# POWER.net
KiCad netlist of a schematic drawn in Altium Designer
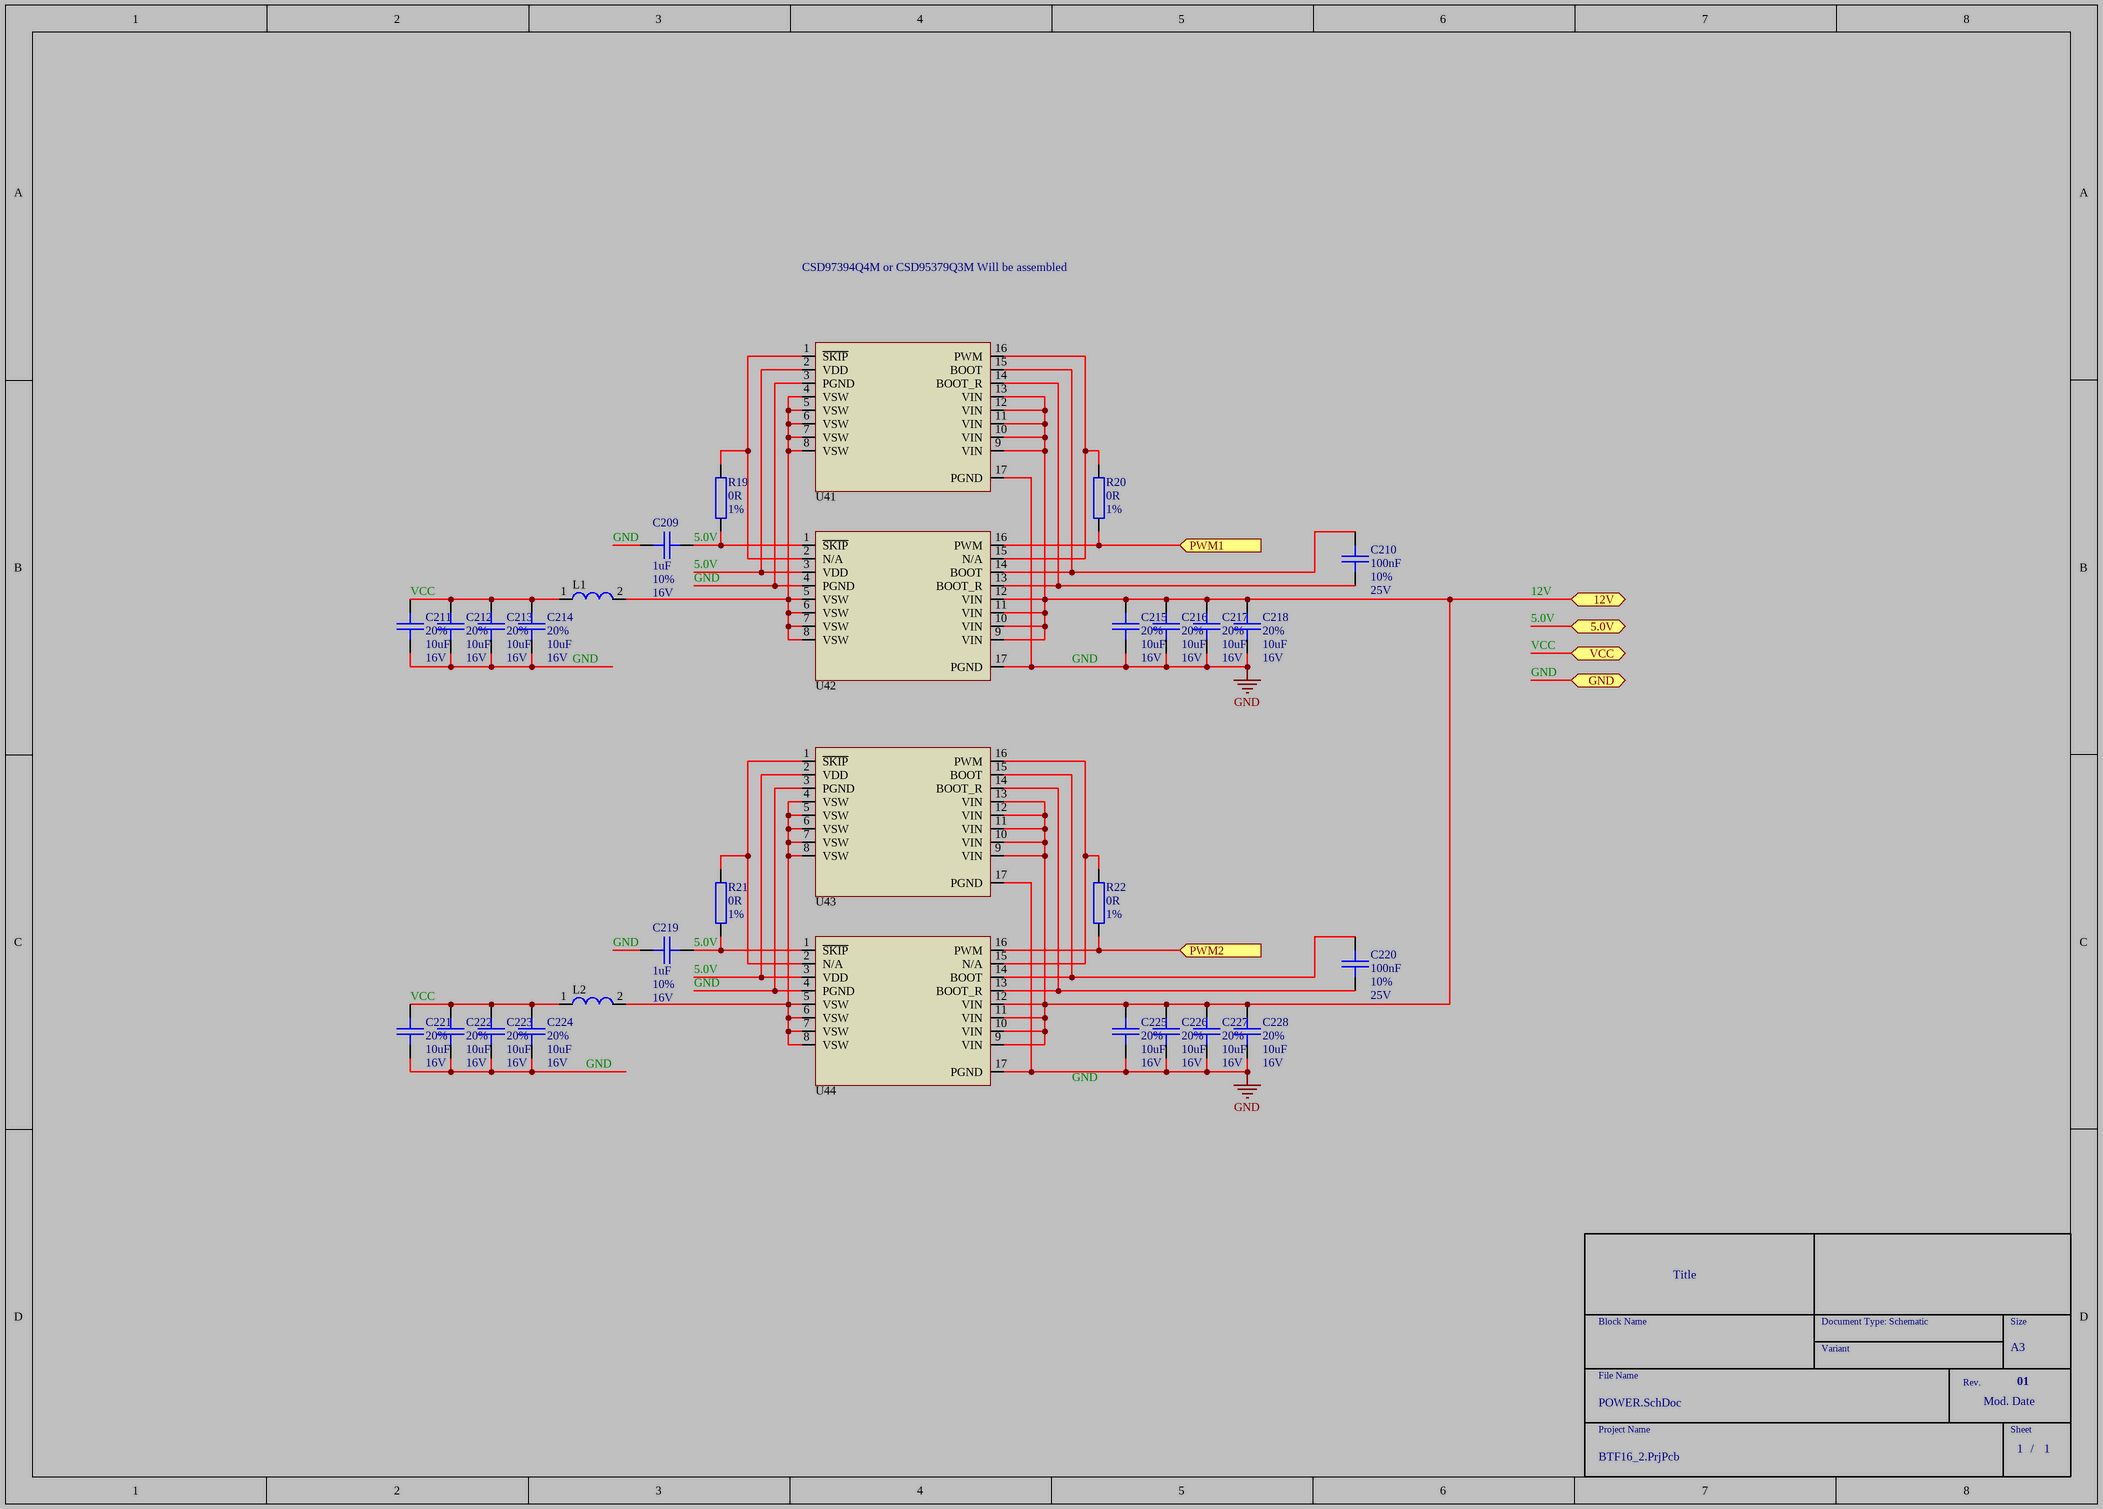
[diagram p0: POWER.SchDoc]

(export (version "E")
  (design (tool "Eeschema 10.0.6"))
  (components
    (comp (ref "C209")
      (value "C")
      (footprint "SMD_0603_CAPC1608X95N")
      (fields
        (field (name "DB_PART_NUMBER") "CAP000023307")
        (field (name "DB_VALUE") "1uF")
        (field (name "DB_TOLERANCE") "10%")
        (field (name "DB_VOLTAGE") "16V")
        (field (name "DB_MANUFACTURER_PART") "KEMET    C0603F105K4RAC")
      )
      (libsource (lib "Database_Libs1") (part "C"))
    )
    (comp (ref "C210")
      (value "C")
      (footprint "SMD_0402_CAPC1005X55N")
      (fields
        (field (name "DB_PART_NUMBER") "CAP000047469")
        (field (name "DB_VALUE") "100nF")
        (field (name "DB_TOLERANCE") "10%")
        (field (name "DB_VOLTAGE") "25V")
        (field (name "DB_MANUFACTURER_PART") "SAMSUNG    CL05A104KA5NNNC")
        (field (name "DB_APPROVED_BY") "VSN")
      )
      (libsource (lib "Database_Libs1") (part "C"))
    )
    (comp (ref "C211")
      (value "C")
      (footprint "SMD_0805_CAPC2012X145N")
      (fields
        (field (name "DB_MANUFACTURER_PART") "KEMET    C0805C106M4PAC")
        (field (name "DB_PART_NUMBER") "CAP000043650")
        (field (name "DB_TOLERANCE") "20%")
        (field (name "DB_VALUE") "10uF")
        (field (name "DB_VOLTAGE") "16V")
      )
      (libsource (lib "Database_Libs1") (part "C"))
    )
    (comp (ref "C212")
      (value "C")
      (footprint "SMD_0805_CAPC2012X145N")
      (fields
        (field (name "DB_MANUFACTURER_PART") "KEMET    C0805C106M4PAC")
        (field (name "DB_PART_NUMBER") "CAP000043650")
        (field (name "DB_TOLERANCE") "20%")
        (field (name "DB_VALUE") "10uF")
        (field (name "DB_VOLTAGE") "16V")
      )
      (libsource (lib "Database_Libs1") (part "C"))
    )
    (comp (ref "C213")
      (value "C")
      (footprint "SMD_0805_CAPC2012X145N")
      (fields
        (field (name "DB_MANUFACTURER_PART") "KEMET    C0805C106M4PAC")
        (field (name "DB_PART_NUMBER") "CAP000043650")
        (field (name "DB_TOLERANCE") "20%")
        (field (name "DB_VALUE") "10uF")
        (field (name "DB_VOLTAGE") "16V")
      )
      (libsource (lib "Database_Libs1") (part "C"))
    )
    (comp (ref "C214")
      (value "C")
      (footprint "SMD_0805_CAPC2012X145N")
      (fields
        (field (name "DB_MANUFACTURER_PART") "KEMET    C0805C106M4PAC")
        (field (name "DB_PART_NUMBER") "CAP000043650")
        (field (name "DB_TOLERANCE") "20%")
        (field (name "DB_VALUE") "10uF")
        (field (name "DB_VOLTAGE") "16V")
      )
      (libsource (lib "Database_Libs1") (part "C"))
    )
    (comp (ref "C215")
      (value "C")
      (footprint "SMD_0805_CAPC2012X145N")
      (fields
        (field (name "DB_MANUFACTURER_PART") "KEMET    C0805C106M4PAC")
        (field (name "DB_PART_NUMBER") "CAP000043650")
        (field (name "DB_TOLERANCE") "20%")
        (field (name "DB_VALUE") "10uF")
        (field (name "DB_VOLTAGE") "16V")
      )
      (libsource (lib "Database_Libs1") (part "C"))
    )
    (comp (ref "C216")
      (value "C")
      (footprint "SMD_0805_CAPC2012X145N")
      (fields
        (field (name "DB_MANUFACTURER_PART") "KEMET    C0805C106M4PAC")
        (field (name "DB_PART_NUMBER") "CAP000043650")
        (field (name "DB_TOLERANCE") "20%")
        (field (name "DB_VALUE") "10uF")
        (field (name "DB_VOLTAGE") "16V")
      )
      (libsource (lib "Database_Libs1") (part "C"))
    )
    (comp (ref "C217")
      (value "C")
      (footprint "SMD_0805_CAPC2012X145N")
      (fields
        (field (name "DB_MANUFACTURER_PART") "KEMET    C0805C106M4PAC")
        (field (name "DB_PART_NUMBER") "CAP000043650")
        (field (name "DB_TOLERANCE") "20%")
        (field (name "DB_VALUE") "10uF")
        (field (name "DB_VOLTAGE") "16V")
      )
      (libsource (lib "Database_Libs1") (part "C"))
    )
    (comp (ref "C218")
      (value "C")
      (footprint "SMD_0805_CAPC2012X145N")
      (fields
        (field (name "DB_MANUFACTURER_PART") "KEMET    C0805C106M4PAC")
        (field (name "DB_PART_NUMBER") "CAP000043650")
        (field (name "DB_TOLERANCE") "20%")
        (field (name "DB_VALUE") "10uF")
        (field (name "DB_VOLTAGE") "16V")
      )
      (libsource (lib "Database_Libs1") (part "C"))
    )
    (comp (ref "C219")
      (value "C")
      (footprint "SMD_0603_CAPC1608X95N")
      (fields
        (field (name "DB_PART_NUMBER") "CAP000023307")
        (field (name "DB_VALUE") "1uF")
        (field (name "DB_TOLERANCE") "10%")
        (field (name "DB_VOLTAGE") "16V")
        (field (name "DB_MANUFACTURER_PART") "KEMET    C0603F105K4RAC")
      )
      (libsource (lib "Database_Libs1") (part "C"))
    )
    (comp (ref "C220")
      (value "C")
      (footprint "SMD_0402_CAPC1005X55N")
      (fields
        (field (name "DB_PART_NUMBER") "CAP000047469")
        (field (name "DB_VALUE") "100nF")
        (field (name "DB_TOLERANCE") "10%")
        (field (name "DB_VOLTAGE") "25V")
        (field (name "DB_MANUFACTURER_PART") "SAMSUNG    CL05A104KA5NNNC")
        (field (name "DB_APPROVED_BY") "VSN")
      )
      (libsource (lib "Database_Libs1") (part "C"))
    )
    (comp (ref "C221")
      (value "C")
      (footprint "SMD_0805_CAPC2012X145N")
      (fields
        (field (name "DB_MANUFACTURER_PART") "KEMET    C0805C106M4PAC")
        (field (name "DB_PART_NUMBER") "CAP000043650")
        (field (name "DB_TOLERANCE") "20%")
        (field (name "DB_VALUE") "10uF")
        (field (name "DB_VOLTAGE") "16V")
      )
      (libsource (lib "Database_Libs1") (part "C"))
    )
    (comp (ref "C222")
      (value "C")
      (footprint "SMD_0805_CAPC2012X145N")
      (fields
        (field (name "DB_MANUFACTURER_PART") "KEMET    C0805C106M4PAC")
        (field (name "DB_PART_NUMBER") "CAP000043650")
        (field (name "DB_TOLERANCE") "20%")
        (field (name "DB_VALUE") "10uF")
        (field (name "DB_VOLTAGE") "16V")
      )
      (libsource (lib "Database_Libs1") (part "C"))
    )
    (comp (ref "C223")
      (value "C")
      (footprint "SMD_0805_CAPC2012X145N")
      (fields
        (field (name "DB_MANUFACTURER_PART") "KEMET    C0805C106M4PAC")
        (field (name "DB_PART_NUMBER") "CAP000043650")
        (field (name "DB_TOLERANCE") "20%")
        (field (name "DB_VALUE") "10uF")
        (field (name "DB_VOLTAGE") "16V")
      )
      (libsource (lib "Database_Libs1") (part "C"))
    )
    (comp (ref "C224")
      (value "C")
      (footprint "SMD_0805_CAPC2012X145N")
      (fields
        (field (name "DB_MANUFACTURER_PART") "KEMET    C0805C106M4PAC")
        (field (name "DB_PART_NUMBER") "CAP000043650")
        (field (name "DB_TOLERANCE") "20%")
        (field (name "DB_VALUE") "10uF")
        (field (name "DB_VOLTAGE") "16V")
      )
      (libsource (lib "Database_Libs1") (part "C"))
    )
    (comp (ref "C225")
      (value "C")
      (footprint "SMD_0805_CAPC2012X145N")
      (fields
        (field (name "DB_MANUFACTURER_PART") "KEMET    C0805C106M4PAC")
        (field (name "DB_PART_NUMBER") "CAP000043650")
        (field (name "DB_TOLERANCE") "20%")
        (field (name "DB_VALUE") "10uF")
        (field (name "DB_VOLTAGE") "16V")
      )
      (libsource (lib "Database_Libs1") (part "C"))
    )
    (comp (ref "C226")
      (value "C")
      (footprint "SMD_0805_CAPC2012X145N")
      (fields
        (field (name "DB_MANUFACTURER_PART") "KEMET    C0805C106M4PAC")
        (field (name "DB_PART_NUMBER") "CAP000043650")
        (field (name "DB_TOLERANCE") "20%")
        (field (name "DB_VALUE") "10uF")
        (field (name "DB_VOLTAGE") "16V")
      )
      (libsource (lib "Database_Libs1") (part "C"))
    )
    (comp (ref "C227")
      (value "C")
      (footprint "SMD_0805_CAPC2012X145N")
      (fields
        (field (name "DB_MANUFACTURER_PART") "KEMET    C0805C106M4PAC")
        (field (name "DB_PART_NUMBER") "CAP000043650")
        (field (name "DB_TOLERANCE") "20%")
        (field (name "DB_VALUE") "10uF")
        (field (name "DB_VOLTAGE") "16V")
      )
      (libsource (lib "Database_Libs1") (part "C"))
    )
    (comp (ref "C228")
      (value "C")
      (footprint "SMD_0805_CAPC2012X145N")
      (fields
        (field (name "DB_MANUFACTURER_PART") "KEMET    C0805C106M4PAC")
        (field (name "DB_PART_NUMBER") "CAP000043650")
        (field (name "DB_TOLERANCE") "20%")
        (field (name "DB_VALUE") "10uF")
        (field (name "DB_VOLTAGE") "16V")
      )
      (libsource (lib "Database_Libs1") (part "C"))
    )
    (comp (ref "L1") (value "470nH") (footprint "SMT_INDM135130X800N") (libsource (lib "DLV") (part "L")))
    (comp (ref "L2") (value "470nH") (footprint "SMT_INDM135130X800N") (libsource (lib "DLV") (part "L")))
    (comp (ref "R19")
      (value "R")
      (footprint "SMD_0603_RESC1608X55N")
      (fields
        (field (name "DB_PART_NUMBER") "RES000008926")
        (field (name "DB_VALUE") "0R")
        (field (name "DB_TOLERANCE") "1%")
        (field (name "DB_MANUFACTURER_PART") "YAGEO    AC0603FR-070RL")
        (field (name "DB_APPROVED_BY") "VSN")
      )
      (libsource (lib "Database_Libs1") (part "R"))
    )
    (comp (ref "R20")
      (value "R")
      (footprint "SMD_0603_RESC1608X55N")
      (fields
        (field (name "DB_PART_NUMBER") "RES000008926")
        (field (name "DB_VALUE") "0R")
        (field (name "DB_TOLERANCE") "1%")
        (field (name "DB_MANUFACTURER_PART") "YAGEO    AC0603FR-070RL")
        (field (name "DB_APPROVED_BY") "VSN")
      )
      (libsource (lib "Database_Libs1") (part "R"))
    )
    (comp (ref "R21")
      (value "R")
      (footprint "SMD_0603_RESC1608X55N")
      (fields
        (field (name "DB_PART_NUMBER") "RES000008926")
        (field (name "DB_VALUE") "0R")
        (field (name "DB_TOLERANCE") "1%")
        (field (name "DB_MANUFACTURER_PART") "YAGEO    AC0603FR-070RL")
        (field (name "DB_APPROVED_BY") "VSN")
      )
      (libsource (lib "Database_Libs1") (part "R"))
    )
    (comp (ref "R22")
      (value "R")
      (footprint "SMD_0603_RESC1608X55N")
      (fields
        (field (name "DB_PART_NUMBER") "RES000008926")
        (field (name "DB_VALUE") "0R")
        (field (name "DB_TOLERANCE") "1%")
        (field (name "DB_MANUFACTURER_PART") "YAGEO    AC0603FR-070RL")
        (field (name "DB_APPROVED_BY") "VSN")
      )
      (libsource (lib "Database_Libs1") (part "R"))
    )
    (comp (ref "U41")
      (value "CSD95379Q3M")
      (footprint "SMD_SON40P330X330X100-17N")
      (description "Texas Instrumendts Buck Boost DC-DC")
      (fields (field (name "DB_MANUFACTURER_PART") "TEXAS INSTRUMENTS  CSD97394Q4M"))
      (libsource (lib "BitCoin") (part "IC_CSD97394Q4M"))
    )
    (comp (ref "U42")
      (value "CSD95379Q3M")
      (footprint "SMD_SON40P330X330X100-17N")
      (description "Texas Instrumendts Buck Boost DC-DC")
      (fields (field (name "DB_MANUFACTURER_PART") "TEXAS INSTRUMENTS  CSD95379Q3M"))
      (libsource (lib "BitCoin") (part "IC_CSD95379Q3M"))
    )
    (comp (ref "U43")
      (value "CSD95379Q3M")
      (footprint "SMD_SON40P330X330X100-17N")
      (description "Texas Instrumendts Buck Boost DC-DC")
      (fields (field (name "DB_MANUFACTURER_PART") "TEXAS INSTRUMENTS  CSD97394Q4M"))
      (libsource (lib "BitCoin") (part "IC_CSD97394Q4M"))
    )
    (comp (ref "U44")
      (value "CSD95379Q3M")
      (footprint "SMD_SON40P330X330X100-17N")
      (description "Texas Instrumendts Buck Boost DC-DC")
      (fields (field (name "DB_MANUFACTURER_PART") "TEXAS INSTRUMENTS  CSD95379Q3M"))
      (libsource (lib "BitCoin") (part "IC_CSD95379Q3M"))
    )
  )
  (nets
    (net (code "1") (name "/5.0V") (class "Default")
      (node (ref "C209") (pin "1") (pinfunction "1_1") (pintype "passive"))
      (node (ref "C219") (pin "1") (pinfunction "1_1") (pintype "passive"))
      (node (ref "R19") (pin "1") (pinfunction "1_1") (pintype "passive"))
      (node (ref "R21") (pin "1") (pinfunction "1_1") (pintype "passive"))
      (node (ref "U41") (pin "2") (pinfunction "VDD_2") (pintype "passive"))
      (node (ref "U42") (pin "1") (pinfunction "~{SKIP}_1") (pintype "passive"))
      (node (ref "U42") (pin "3") (pinfunction "VDD_3") (pintype "passive"))
      (node (ref "U43") (pin "2") (pinfunction "VDD_2") (pintype "passive"))
      (node (ref "U44") (pin "1") (pinfunction "~{SKIP}_1") (pintype "passive"))
      (node (ref "U44") (pin "3") (pinfunction "VDD_3") (pintype "passive"))
    )
    (net (code "2") (name "/12V") (class "Default")
      (node (ref "C215") (pin "1") (pinfunction "1_1") (pintype "passive"))
      (node (ref "C216") (pin "1") (pinfunction "1_1") (pintype "passive"))
      (node (ref "C217") (pin "1") (pinfunction "1_1") (pintype "passive"))
      (node (ref "C218") (pin "1") (pinfunction "1_1") (pintype "passive"))
      (node (ref "C225") (pin "1") (pinfunction "1_1") (pintype "passive"))
      (node (ref "C226") (pin "1") (pinfunction "1_1") (pintype "passive"))
      (node (ref "C227") (pin "1") (pinfunction "1_1") (pintype "passive"))
      (node (ref "C228") (pin "1") (pinfunction "1_1") (pintype "passive"))
      (node (ref "U41") (pin "10") (pinfunction "VIN_10") (pintype "passive"))
      (node (ref "U41") (pin "11") (pinfunction "VIN_11") (pintype "passive"))
      (node (ref "U41") (pin "12") (pinfunction "VIN_12") (pintype "passive"))
      (node (ref "U41") (pin "13") (pinfunction "VIN_13") (pintype "passive"))
      (node (ref "U41") (pin "9") (pinfunction "VIN_9") (pintype "passive"))
      (node (ref "U42") (pin "10") (pinfunction "VIN_10") (pintype "passive"))
      (node (ref "U42") (pin "11") (pinfunction "VIN_11") (pintype "passive"))
      (node (ref "U42") (pin "12") (pinfunction "VIN_12") (pintype "passive"))
      (node (ref "U42") (pin "9") (pinfunction "VIN_9") (pintype "passive"))
      (node (ref "U43") (pin "10") (pinfunction "VIN_10") (pintype "passive"))
      (node (ref "U43") (pin "11") (pinfunction "VIN_11") (pintype "passive"))
      (node (ref "U43") (pin "12") (pinfunction "VIN_12") (pintype "passive"))
      (node (ref "U43") (pin "13") (pinfunction "VIN_13") (pintype "passive"))
      (node (ref "U43") (pin "9") (pinfunction "VIN_9") (pintype "passive"))
      (node (ref "U44") (pin "10") (pinfunction "VIN_10") (pintype "passive"))
      (node (ref "U44") (pin "11") (pinfunction "VIN_11") (pintype "passive"))
      (node (ref "U44") (pin "12") (pinfunction "VIN_12") (pintype "passive"))
      (node (ref "U44") (pin "9") (pinfunction "VIN_9") (pintype "passive"))
    )
    (net (code "3") (name "/PWM1") (class "Default")
      (node (ref "R20") (pin "1") (pinfunction "1_1") (pintype "passive"))
      (node (ref "U42") (pin "16") (pinfunction "PWM_16") (pintype "passive"))
    )
    (net (code "4") (name "/PWM2") (class "Default")
      (node (ref "R22") (pin "1") (pinfunction "1_1") (pintype "passive"))
      (node (ref "U44") (pin "16") (pinfunction "PWM_16") (pintype "passive"))
    )
    (net (code "5") (name "/VCC") (class "Default")
      (node (ref "C211") (pin "1") (pinfunction "1_1") (pintype "passive"))
      (node (ref "C212") (pin "1") (pinfunction "1_1") (pintype "passive"))
      (node (ref "C213") (pin "1") (pinfunction "1_1") (pintype "passive"))
      (node (ref "C214") (pin "1") (pinfunction "1_1") (pintype "passive"))
      (node (ref "C221") (pin "1") (pinfunction "1_1") (pintype "passive"))
      (node (ref "C222") (pin "1") (pinfunction "1_1") (pintype "passive"))
      (node (ref "C223") (pin "1") (pinfunction "1_1") (pintype "passive"))
      (node (ref "C224") (pin "1") (pinfunction "1_1") (pintype "passive"))
      (node (ref "L1") (pin "1") (pinfunction "1_1") (pintype "passive"))
      (node (ref "L2") (pin "1") (pinfunction "1_1") (pintype "passive"))
    )
    (net (code "6") (name "GND") (class "Default")
      (node (ref "C209") (pin "2") (pinfunction "2_2") (pintype "passive"))
      (node (ref "C211") (pin "2") (pinfunction "2_2") (pintype "passive"))
      (node (ref "C212") (pin "2") (pinfunction "2_2") (pintype "passive"))
      (node (ref "C213") (pin "2") (pinfunction "2_2") (pintype "passive"))
      (node (ref "C214") (pin "2") (pinfunction "2_2") (pintype "passive"))
      (node (ref "C215") (pin "2") (pinfunction "2_2") (pintype "passive"))
      (node (ref "C216") (pin "2") (pinfunction "2_2") (pintype "passive"))
      (node (ref "C217") (pin "2") (pinfunction "2_2") (pintype "passive"))
      (node (ref "C218") (pin "2") (pinfunction "2_2") (pintype "passive"))
      (node (ref "C219") (pin "2") (pinfunction "2_2") (pintype "passive"))
      (node (ref "C221") (pin "2") (pinfunction "2_2") (pintype "passive"))
      (node (ref "C222") (pin "2") (pinfunction "2_2") (pintype "passive"))
      (node (ref "C223") (pin "2") (pinfunction "2_2") (pintype "passive"))
      (node (ref "C224") (pin "2") (pinfunction "2_2") (pintype "passive"))
      (node (ref "C225") (pin "2") (pinfunction "2_2") (pintype "passive"))
      (node (ref "C226") (pin "2") (pinfunction "2_2") (pintype "passive"))
      (node (ref "C227") (pin "2") (pinfunction "2_2") (pintype "passive"))
      (node (ref "C228") (pin "2") (pinfunction "2_2") (pintype "passive"))
      (node (ref "U41") (pin "17") (pinfunction "PGND_17") (pintype "passive"))
      (node (ref "U41") (pin "3") (pinfunction "PGND_3") (pintype "passive"))
      (node (ref "U42") (pin "17") (pinfunction "PGND_17") (pintype "passive"))
      (node (ref "U42") (pin "4") (pinfunction "PGND_4") (pintype "passive"))
      (node (ref "U43") (pin "17") (pinfunction "PGND_17") (pintype "passive"))
      (node (ref "U43") (pin "3") (pinfunction "PGND_3") (pintype "passive"))
      (node (ref "U44") (pin "17") (pinfunction "PGND_17") (pintype "passive"))
      (node (ref "U44") (pin "4") (pinfunction "PGND_4") (pintype "passive"))
    )
    (net (code "7") (name "Net-(L1-Pad2)") (class "Default")
      (node (ref "L1") (pin "2") (pinfunction "2_2") (pintype "passive"))
      (node (ref "U41") (pin "4") (pinfunction "VSW_4") (pintype "passive"))
      (node (ref "U41") (pin "5") (pinfunction "VSW_5") (pintype "passive"))
      (node (ref "U41") (pin "6") (pinfunction "VSW_6") (pintype "passive"))
      (node (ref "U41") (pin "7") (pinfunction "VSW_7") (pintype "passive"))
      (node (ref "U41") (pin "8") (pinfunction "VSW_8") (pintype "passive"))
      (node (ref "U42") (pin "5") (pinfunction "VSW_5") (pintype "passive"))
      (node (ref "U42") (pin "6") (pinfunction "VSW_6") (pintype "passive"))
      (node (ref "U42") (pin "7") (pinfunction "VSW_7") (pintype "passive"))
      (node (ref "U42") (pin "8") (pinfunction "VSW_8") (pintype "passive"))
    )
    (net (code "8") (name "Net-(L2-Pad2)") (class "Default")
      (node (ref "L2") (pin "2") (pinfunction "2_2") (pintype "passive"))
      (node (ref "U43") (pin "4") (pinfunction "VSW_4") (pintype "passive"))
      (node (ref "U43") (pin "5") (pinfunction "VSW_5") (pintype "passive"))
      (node (ref "U43") (pin "6") (pinfunction "VSW_6") (pintype "passive"))
      (node (ref "U43") (pin "7") (pinfunction "VSW_7") (pintype "passive"))
      (node (ref "U43") (pin "8") (pinfunction "VSW_8") (pintype "passive"))
      (node (ref "U44") (pin "5") (pinfunction "VSW_5") (pintype "passive"))
      (node (ref "U44") (pin "6") (pinfunction "VSW_6") (pintype "passive"))
      (node (ref "U44") (pin "7") (pinfunction "VSW_7") (pintype "passive"))
      (node (ref "U44") (pin "8") (pinfunction "VSW_8") (pintype "passive"))
    )
    (net (code "9") (name "Net-(U41-BOOT)") (class "Default")
      (node (ref "C210") (pin "1") (pinfunction "1_1") (pintype "passive"))
      (node (ref "U41") (pin "15") (pinfunction "BOOT_15") (pintype "passive"))
      (node (ref "U42") (pin "14") (pinfunction "BOOT_14") (pintype "passive"))
    )
    (net (code "10") (name "Net-(U41-BOOT_R)") (class "Default")
      (node (ref "C210") (pin "2") (pinfunction "2_2") (pintype "passive"))
      (node (ref "U41") (pin "14") (pinfunction "BOOT_R_14") (pintype "passive"))
      (node (ref "U42") (pin "13") (pinfunction "BOOT_R_13") (pintype "passive"))
    )
    (net (code "11") (name "Net-(U41-PWM)") (class "Default")
      (node (ref "R20") (pin "2") (pinfunction "2_2") (pintype "passive"))
      (node (ref "U41") (pin "16") (pinfunction "PWM_16") (pintype "passive"))
      (node (ref "U42") (pin "15") (pinfunction "N/A_15") (pintype "passive"))
    )
    (net (code "12") (name "Net-(U41-~{SKIP})") (class "Default")
      (node (ref "R19") (pin "2") (pinfunction "2_2") (pintype "passive"))
      (node (ref "U41") (pin "1") (pinfunction "~{SKIP}_1") (pintype "passive"))
      (node (ref "U42") (pin "2") (pinfunction "N/A_2") (pintype "passive"))
    )
    (net (code "13") (name "Net-(U43-BOOT)") (class "Default")
      (node (ref "C220") (pin "1") (pinfunction "1_1") (pintype "passive"))
      (node (ref "U43") (pin "15") (pinfunction "BOOT_15") (pintype "passive"))
      (node (ref "U44") (pin "14") (pinfunction "BOOT_14") (pintype "passive"))
    )
    (net (code "14") (name "Net-(U43-BOOT_R)") (class "Default")
      (node (ref "C220") (pin "2") (pinfunction "2_2") (pintype "passive"))
      (node (ref "U43") (pin "14") (pinfunction "BOOT_R_14") (pintype "passive"))
      (node (ref "U44") (pin "13") (pinfunction "BOOT_R_13") (pintype "passive"))
    )
    (net (code "15") (name "Net-(U43-PWM)") (class "Default")
      (node (ref "R22") (pin "2") (pinfunction "2_2") (pintype "passive"))
      (node (ref "U43") (pin "16") (pinfunction "PWM_16") (pintype "passive"))
      (node (ref "U44") (pin "15") (pinfunction "N/A_15") (pintype "passive"))
    )
    (net (code "16") (name "Net-(U43-~{SKIP})") (class "Default")
      (node (ref "R21") (pin "2") (pinfunction "2_2") (pintype "passive"))
      (node (ref "U43") (pin "1") (pinfunction "~{SKIP}_1") (pintype "passive"))
      (node (ref "U44") (pin "2") (pinfunction "N/A_2") (pintype "passive"))
    )
  )
)
